# MINI_SAM_D51_017.net
KiCad netlist of a schematic drawn in EAGLE
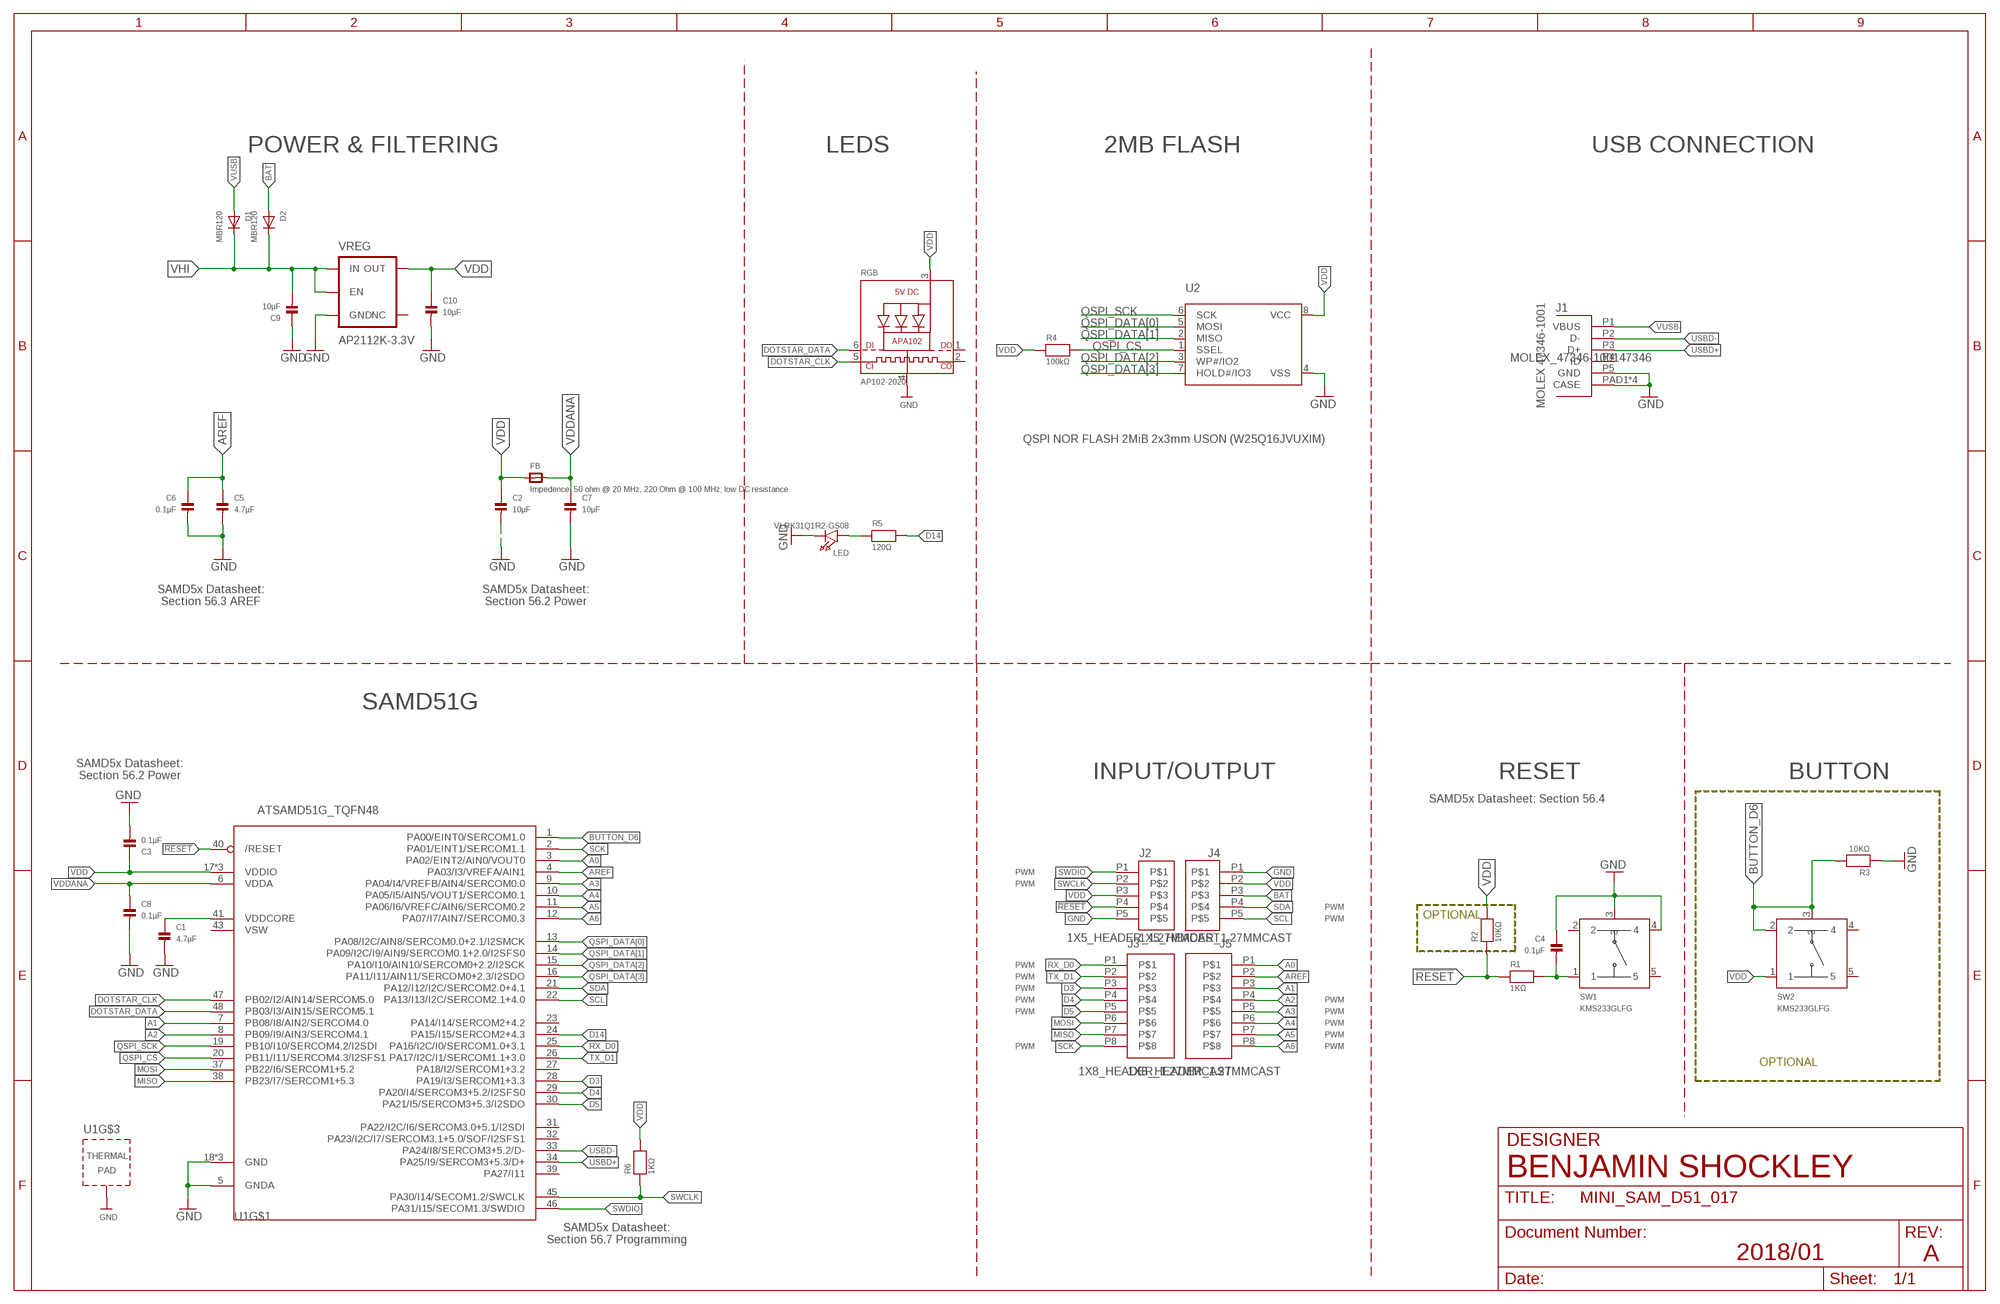
[diagram p0: schematic, sheet 1]

(export (version "E")
  (design (tool "Eeschema 10.0.6"))
  (components
    (comp (ref "C1")
      (value "4.7µF")
      (footprint "eagle-import:_0603MP")
      (libsource (lib "eagle-import") (part "CAP_CERAMIC_0603MP"))
    )
    (comp (ref "C2")
      (value "10µF")
      (footprint "eagle-import:_0603MP")
      (libsource (lib "eagle-import") (part "CAP_CERAMIC_0603MP"))
    )
    (comp (ref "C3")
      (value "0.1µF")
      (footprint "eagle-import:_0603MP")
      (libsource (lib "eagle-import") (part "CAP_CERAMIC_0603MP"))
    )
    (comp (ref "C4")
      (value "0.1µF")
      (footprint "eagle-import:_0603MP")
      (libsource (lib "eagle-import") (part "CAP_CERAMIC_0603MP"))
    )
    (comp (ref "C5")
      (value "4.7µF")
      (footprint "eagle-import:_0603MP")
      (libsource (lib "eagle-import") (part "CAP_CERAMIC_0603MP"))
    )
    (comp (ref "C6")
      (value "0.1µF")
      (footprint "eagle-import:_0603MP")
      (libsource (lib "eagle-import") (part "CAP_CERAMIC_0603MP"))
    )
    (comp (ref "C7")
      (value "10µF")
      (footprint "eagle-import:_0603MP")
      (libsource (lib "eagle-import") (part "CAP_CERAMIC_0603MP"))
    )
    (comp (ref "C8")
      (value "0.1µF")
      (footprint "eagle-import:_0603MP")
      (libsource (lib "eagle-import") (part "CAP_CERAMIC_0603MP"))
    )
    (comp (ref "C9")
      (value "10µF")
      (footprint "eagle-import:_0603MP")
      (libsource (lib "eagle-import") (part "CAP_CERAMIC_0603MP"))
    )
    (comp (ref "C10")
      (value "10µF")
      (footprint "eagle-import:_0603MP")
      (libsource (lib "eagle-import") (part "CAP_CERAMIC_0603MP"))
    )
    (comp (ref "D1")
      (value "MBR120")
      (footprint "eagle-import:SOD-123FL")
      (libsource (lib "eagle-import") (part "DIODE_SOD-123FL"))
    )
    (comp (ref "D2")
      (value "MBR120")
      (footprint "eagle-import:SOD-123FL")
      (libsource (lib "eagle-import") (part "DIODE_SOD-123FL"))
    )
    (comp (ref "FB")
      (value "Impedence: 50 ohm @ 20 MHz, 220 Ohm @ 100 MHz; low DC resistance")
      (footprint "eagle-import:_0603MP")
      (libsource (lib "eagle-import") (part "FERRITE_0603MP"))
    )
    (comp (ref "J1")
      (value "MOLEX_47346-100147346")
      (footprint "eagle-import:MOLEX_47346-1001")
      (libsource (lib "eagle-import") (part "MOLEX_47346-100147346"))
    )
    (comp (ref "J2")
      (value "1X5_HEADER_1.27MMCAST")
      (footprint "eagle-import:1X5_HEADER_1.27MM_CASTELLATED")
      (libsource (lib "eagle-import") (part "1X5_HEADER_1.27MMCAST"))
    )
    (comp (ref "J3")
      (value "1X8_HEADER_1.27MMCAST")
      (footprint "eagle-import:1X8_HEADER_1.27MM_CASTELLATED")
      (libsource (lib "eagle-import") (part "1X8_HEADER_1.27MMCAST"))
    )
    (comp (ref "J4")
      (value "1X5_HEADER_1.27MMCAST")
      (footprint "eagle-import:1X5_HEADER_1.27MM_CASTELLATED")
      (libsource (lib "eagle-import") (part "1X5_HEADER_1.27MMCAST"))
    )
    (comp (ref "J5")
      (value "1X8_HEADER_1.27MMCAST")
      (footprint "eagle-import:1X8_HEADER_1.27MM_CASTELLATED")
      (libsource (lib "eagle-import") (part "1X8_HEADER_1.27MMCAST"))
    )
    (comp (ref "LED")
      (value "VLRK31Q1R2-GS08")
      (footprint "eagle-import:REVERSE_MOUNT_LED")
      (libsource (lib "eagle-import") (part "REVERSEMOUNTLED"))
    )
    (comp (ref "R1")
      (value "1KΩ")
      (footprint "eagle-import:_0603MP")
      (libsource (lib "eagle-import") (part "RESISTOR_0603MP"))
    )
    (comp (ref "R2")
      (value "10KΩ")
      (footprint "eagle-import:_0603MP")
      (libsource (lib "eagle-import") (part "RESISTOR_0603MP"))
    )
    (comp (ref "R3")
      (value "10KΩ")
      (footprint "eagle-import:_0603MP")
      (libsource (lib "eagle-import") (part "RESISTOR_0603MP"))
    )
    (comp (ref "R4")
      (value "100kΩ")
      (footprint "eagle-import:_0603MP")
      (libsource (lib "eagle-import") (part "RESISTOR_0603MP"))
    )
    (comp (ref "R5")
      (value "120Ω")
      (footprint "eagle-import:_0603MP")
      (libsource (lib "eagle-import") (part "RESISTOR_0603MP"))
    )
    (comp (ref "R6")
      (value "1KΩ")
      (footprint "eagle-import:_0603MP")
      (libsource (lib "eagle-import") (part "RESISTOR_0603MP"))
    )
    (comp (ref "RGB")
      (value "AP102-2020")
      (footprint "eagle-import:APA102_2020")
      (libsource (lib "eagle-import") (part "APA1022020"))
    )
    (comp (ref "SW1")
      (value "KMS233GLFG")
      (footprint "eagle-import:KMS_SWITCH")
      (libsource (lib "eagle-import") (part "KMS_SWITCHKMS"))
    )
    (comp (ref "SW2")
      (value "KMS233GLFG")
      (footprint "eagle-import:KMS_SWITCH")
      (libsource (lib "eagle-import") (part "KMS_SWITCHKMS"))
    )
    (comp (ref "U1")
      (value "ATSAMD51G_TQFN48")
      (footprint "eagle-import:TQFN48_7MM")
      (libsource (lib "eagle-import") (part "ATSAMD51G_TQFN48"))
    )
    (comp (ref "U2")
      (value "QSPI NOR FLASH 2MiB 2x3mm USON (W25Q16JVUXIM)")
      (footprint "eagle-import:USON8")
      (libsource (lib "eagle-import") (part "SPIFLASH_8PINUX"))
    )
    (comp (ref "VREG")
      (value "AP2112K-3.3V")
      (footprint "eagle-import:SOT23-5")
      (libsource (lib "eagle-import") (part "V_REG_AP2112K-3.3V"))
    )
  )
  (nets
    (net (code "1") (name "/VSW") (class "Default")
      (node (ref "U1") (pin "43") (pinfunction "VSW_43") (pintype "power_in"))
    )
    (net (code "2") (name "/~{RESET}") (class "Default")
      (node (ref "J2") (pin "P4") (pinfunction "P$4_P4") (pintype "bidirectional"))
      (node (ref "R1") (pin "1") (pinfunction "1_1") (pintype "passive"))
      (node (ref "R2") (pin "1") (pinfunction "1_1") (pintype "passive"))
      (node (ref "U1") (pin "40") (pinfunction "/RESET_40") (pintype "bidirectional"))
    )
    (net (code "3") (name "A0") (class "Default")
      (node (ref "J5") (pin "P1") (pinfunction "P$1_P1") (pintype "bidirectional"))
      (node (ref "U1") (pin "3") (pinfunction "PA02/EINT2/AIN0/VOUT0_3") (pintype "bidirectional"))
    )
    (net (code "4") (name "A1") (class "Default")
      (node (ref "J5") (pin "P3") (pinfunction "P$3_P3") (pintype "bidirectional"))
      (node (ref "U1") (pin "7") (pinfunction "PB08/I8/AIN2/SERCOM4.0_7") (pintype "bidirectional"))
    )
    (net (code "5") (name "A2") (class "Default")
      (node (ref "J5") (pin "P4") (pinfunction "P$4_P4") (pintype "bidirectional"))
      (node (ref "U1") (pin "8") (pinfunction "PB09/I9/AIN3/SERCOM4.1_8") (pintype "bidirectional"))
    )
    (net (code "6") (name "A3") (class "Default")
      (node (ref "J5") (pin "P5") (pinfunction "P$5_P5") (pintype "bidirectional"))
      (node (ref "U1") (pin "9") (pinfunction "PA04/I4/VREFB/AIN4/SERCOM0.0_9") (pintype "bidirectional"))
    )
    (net (code "7") (name "A4") (class "Default")
      (node (ref "J5") (pin "P6") (pinfunction "P$6_P6") (pintype "bidirectional"))
      (node (ref "U1") (pin "10") (pinfunction "PA05/I5/AIN5/VOUT1/SERCOM0.1_10") (pintype "bidirectional"))
    )
    (net (code "8") (name "A5") (class "Default")
      (node (ref "J5") (pin "P7") (pinfunction "P$7_P7") (pintype "bidirectional"))
      (node (ref "U1") (pin "11") (pinfunction "PA06/I6/VREFC/AIN6/SERCOM0.2_11") (pintype "bidirectional"))
    )
    (net (code "9") (name "A6") (class "Default")
      (node (ref "J5") (pin "P8") (pinfunction "P$8_P8") (pintype "bidirectional"))
      (node (ref "U1") (pin "12") (pinfunction "PA07/I7/AIN7/SERCOM0.3_12") (pintype "bidirectional"))
    )
    (net (code "10") (name "AREF") (class "Default")
      (node (ref "C5") (pin "1") (pinfunction "P$1_1") (pintype "passive"))
      (node (ref "C6") (pin "1") (pinfunction "P$1_1") (pintype "passive"))
      (node (ref "J5") (pin "P2") (pinfunction "P$2_P2") (pintype "bidirectional"))
      (node (ref "U1") (pin "4") (pinfunction "PA03/I3/VREFA/AIN1_4") (pintype "bidirectional"))
    )
    (net (code "11") (name "BAT") (class "Default")
      (node (ref "D2") (pin "A") (pinfunction "A_A") (pintype "passive"))
      (node (ref "J4") (pin "P3") (pinfunction "P$3_P3") (pintype "bidirectional"))
    )
    (net (code "12") (name "BUTTON_D6") (class "Default")
      (node (ref "R3") (pin "2") (pinfunction "2_2") (pintype "passive"))
      (node (ref "SW2") (pin "2") (pinfunction "2_2") (pintype "bidirectional"))
      (node (ref "SW2") (pin "3") (pinfunction "3_3") (pintype "bidirectional"))
      (node (ref "U1") (pin "1") (pinfunction "PA00/EINT0/SERCOM1.0_1") (pintype "bidirectional"))
    )
    (net (code "13") (name "D3") (class "Default")
      (node (ref "J3") (pin "P3") (pinfunction "P$3_P3") (pintype "bidirectional"))
      (node (ref "U1") (pin "28") (pinfunction "PA19/I3/SERCOM1+3.3_28") (pintype "bidirectional"))
    )
    (net (code "14") (name "D4") (class "Default")
      (node (ref "J3") (pin "P4") (pinfunction "P$4_P4") (pintype "bidirectional"))
      (node (ref "U1") (pin "29") (pinfunction "PA20/I4/SERCOM3+5.2/I2SFS0_29") (pintype "bidirectional"))
    )
    (net (code "15") (name "D5") (class "Default")
      (node (ref "J3") (pin "P5") (pinfunction "P$5_P5") (pintype "bidirectional"))
      (node (ref "U1") (pin "30") (pinfunction "PA21/I5/SERCOM3+5.3/I2SDO_30") (pintype "bidirectional"))
    )
    (net (code "16") (name "D14") (class "Default")
      (node (ref "R5") (pin "2") (pinfunction "2_2") (pintype "passive"))
      (node (ref "U1") (pin "24") (pinfunction "PA15/I15/SERCOM2+4.3_24") (pintype "bidirectional"))
    )
    (net (code "17") (name "DOTSTAR_CLK") (class "Default")
      (node (ref "RGB") (pin "5") (pinfunction "CKI_5") (pintype "input"))
      (node (ref "U1") (pin "47") (pinfunction "PB02/I2/AIN14/SERCOM5.0_47") (pintype "bidirectional"))
    )
    (net (code "18") (name "DOTSTAR_DATA") (class "Default")
      (node (ref "RGB") (pin "6") (pinfunction "DI_6") (pintype "input"))
      (node (ref "U1") (pin "48") (pinfunction "PB03/I3/AIN15/SERCOM5.1_48") (pintype "bidirectional"))
    )
    (net (code "19") (name "GND") (class "Default")
      (node (ref "C1") (pin "2") (pinfunction "P$2_2") (pintype "passive"))
      (node (ref "C10") (pin "2") (pinfunction "P$2_2") (pintype "passive"))
      (node (ref "C2") (pin "2") (pinfunction "P$2_2") (pintype "passive"))
      (node (ref "C3") (pin "2") (pinfunction "P$2_2") (pintype "passive"))
      (node (ref "C4") (pin "1") (pinfunction "P$1_1") (pintype "passive"))
      (node (ref "C5") (pin "2") (pinfunction "P$2_2") (pintype "passive"))
      (node (ref "C6") (pin "2") (pinfunction "P$2_2") (pintype "passive"))
      (node (ref "C7") (pin "2") (pinfunction "P$2_2") (pintype "passive"))
      (node (ref "C8") (pin "2") (pinfunction "P$2_2") (pintype "passive"))
      (node (ref "C9") (pin "1") (pinfunction "P$1_1") (pintype "passive"))
      (node (ref "J1") (pin "P5") (pinfunction "GND_P5") (pintype "power_in"))
      (node (ref "J1") (pin "PAD1") (pinfunction "CASE_PAD1") (pintype "bidirectional"))
      (node (ref "J1") (pin "PAD2") (pinfunction "CASE_PAD2") (pintype "bidirectional"))
      (node (ref "J1") (pin "PAD3") (pinfunction "CASE_PAD3") (pintype "bidirectional"))
      (node (ref "J1") (pin "PAD4") (pinfunction "CASE_PAD4") (pintype "bidirectional"))
      (node (ref "J2") (pin "P5") (pinfunction "P$5_P5") (pintype "bidirectional"))
      (node (ref "J4") (pin "P1") (pinfunction "P$1_P1") (pintype "bidirectional"))
      (node (ref "LED") (pin "C") (pinfunction "C_C") (pintype "passive"))
      (node (ref "R3") (pin "1") (pinfunction "1_1") (pintype "passive"))
      (node (ref "RGB") (pin "4") (pinfunction "GND_4") (pintype "power_in"))
      (node (ref "SW1") (pin "3") (pinfunction "3_3") (pintype "bidirectional"))
      (node (ref "SW1") (pin "4") (pinfunction "4_4") (pintype "bidirectional"))
      (node (ref "U1") (pin "18") (pinfunction "GND_18") (pintype "power_in"))
      (node (ref "U1") (pin "35") (pinfunction "GND_35") (pintype "power_in"))
      (node (ref "U1") (pin "42") (pinfunction "GND_42") (pintype "power_in"))
      (node (ref "U1") (pin "5") (pinfunction "GNDA_5") (pintype "power_in"))
      (node (ref "U1") (pin "THERMAL") (pinfunction "TP_THERMAL") (pintype "power_in"))
      (node (ref "U2") (pin "4") (pinfunction "VSS_4") (pintype "bidirectional"))
      (node (ref "VREG") (pin "2") (pinfunction "GND_2") (pintype "input"))
    )
    (net (code "20") (name "MISO") (class "Default")
      (node (ref "J3") (pin "P7") (pinfunction "P$7_P7") (pintype "bidirectional"))
      (node (ref "U1") (pin "38") (pinfunction "PB23/I7/SERCOM1+5.3_38") (pintype "bidirectional"))
    )
    (net (code "21") (name "MOSI") (class "Default")
      (node (ref "J3") (pin "P6") (pinfunction "P$6_P6") (pintype "bidirectional"))
      (node (ref "U1") (pin "37") (pinfunction "PB22/I6/SERCOM1+5.2_37") (pintype "bidirectional"))
    )
    (net (code "22") (name "Net-(C1-P$1)") (class "Default")
      (node (ref "C1") (pin "1") (pinfunction "P$1_1") (pintype "passive"))
      (node (ref "U1") (pin "41") (pinfunction "VDDCORE_41") (pintype "power_in"))
    )
    (net (code "23") (name "Net-(C4-P$2)") (class "Default")
      (node (ref "C4") (pin "2") (pinfunction "P$2_2") (pintype "passive"))
      (node (ref "R1") (pin "2") (pinfunction "2_2") (pintype "passive"))
      (node (ref "SW1") (pin "1") (pinfunction "1_1") (pintype "bidirectional"))
    )
    (net (code "24") (name "Net-(LED-PadA)") (class "Default")
      (node (ref "LED") (pin "A") (pinfunction "A_A") (pintype "passive"))
      (node (ref "R5") (pin "1") (pinfunction "1_1") (pintype "passive"))
    )
    (net (code "25") (name "QSPI_CS") (class "Default")
      (node (ref "R4") (pin "2") (pinfunction "2_2") (pintype "passive"))
      (node (ref "U1") (pin "20") (pinfunction "PB11/I11/SERCOM4.3/I2SFS1_20") (pintype "bidirectional"))
      (node (ref "U2") (pin "1") (pinfunction "SSEL_1") (pintype "bidirectional"))
    )
    (net (code "26") (name "QSPI_DATA[0]") (class "Default")
      (node (ref "U1") (pin "13") (pinfunction "PA08/I2C/AIN8/SERCOM0.0+2.1/I2SMCK_13") (pintype "bidirectional"))
      (node (ref "U2") (pin "5") (pinfunction "MOSI_5") (pintype "bidirectional"))
    )
    (net (code "27") (name "QSPI_DATA[1]") (class "Default")
      (node (ref "U1") (pin "14") (pinfunction "PA09/I2C/I9/AIN9/SERCOM0.1+2.0/I2SFS0_14") (pintype "bidirectional"))
      (node (ref "U2") (pin "2") (pinfunction "MISO_2") (pintype "bidirectional"))
    )
    (net (code "28") (name "QSPI_DATA[2]") (class "Default")
      (node (ref "U1") (pin "15") (pinfunction "PA10/I10/AIN10/SERCOM0+2.2/I2SCK_15") (pintype "bidirectional"))
      (node (ref "U2") (pin "3") (pinfunction "WP#/IO2_3") (pintype "bidirectional"))
    )
    (net (code "29") (name "QSPI_DATA[3]") (class "Default")
      (node (ref "U1") (pin "16") (pinfunction "PA11/I11/AIN11/SERCOM0+2.3/I2SDO_16") (pintype "bidirectional"))
      (node (ref "U2") (pin "7") (pinfunction "HOLD#/IO3_7") (pintype "bidirectional"))
    )
    (net (code "30") (name "QSPI_SCK") (class "Default")
      (node (ref "U1") (pin "19") (pinfunction "PB10/I10/SERCOM4.2/I2SDI_19") (pintype "bidirectional"))
      (node (ref "U2") (pin "6") (pinfunction "SCK_6") (pintype "bidirectional"))
    )
    (net (code "31") (name "RX_D0") (class "Default")
      (node (ref "J3") (pin "P1") (pinfunction "P$1_P1") (pintype "bidirectional"))
      (node (ref "U1") (pin "25") (pinfunction "PA16/I2C/I0/SERCOM1.0+3.1_25") (pintype "bidirectional"))
    )
    (net (code "32") (name "SCK") (class "Default")
      (node (ref "J3") (pin "P8") (pinfunction "P$8_P8") (pintype "bidirectional"))
      (node (ref "U1") (pin "2") (pinfunction "PA01/EINT1/SERCOM1.1_2") (pintype "bidirectional"))
    )
    (net (code "33") (name "SCL") (class "Default")
      (node (ref "J4") (pin "P5") (pinfunction "P$5_P5") (pintype "bidirectional"))
      (node (ref "U1") (pin "22") (pinfunction "PA13/I13/I2C/SERCOM2.1+4.0_22") (pintype "bidirectional"))
    )
    (net (code "34") (name "SDA") (class "Default")
      (node (ref "J4") (pin "P4") (pinfunction "P$4_P4") (pintype "bidirectional"))
      (node (ref "U1") (pin "21") (pinfunction "PA12/I12/I2C/SERCOM2.0+4.1_21") (pintype "bidirectional"))
    )
    (net (code "35") (name "SWCLK") (class "Default")
      (node (ref "J2") (pin "P2") (pinfunction "P$2_P2") (pintype "bidirectional"))
      (node (ref "R6") (pin "1") (pinfunction "1_1") (pintype "passive"))
      (node (ref "U1") (pin "45") (pinfunction "PA30/I14/SECOM1.2/SWCLK_45") (pintype "bidirectional"))
    )
    (net (code "36") (name "SWDIO") (class "Default")
      (node (ref "J2") (pin "P1") (pinfunction "P$1_P1") (pintype "bidirectional"))
      (node (ref "U1") (pin "46") (pinfunction "PA31/I15/SECOM1.3/SWDIO_46") (pintype "bidirectional"))
    )
    (net (code "37") (name "TX_D1") (class "Default")
      (node (ref "J3") (pin "P2") (pinfunction "P$2_P2") (pintype "bidirectional"))
      (node (ref "U1") (pin "26") (pinfunction "PA17/I2C/I1/SERCOM1.1+3.0_26") (pintype "bidirectional"))
    )
    (net (code "38") (name "USBD+") (class "Default")
      (node (ref "J1") (pin "P3") (pinfunction "D+_P3") (pintype "bidirectional"))
      (node (ref "U1") (pin "34") (pinfunction "PA25/I9/SERCOM3+5.3/D+_34") (pintype "bidirectional"))
    )
    (net (code "39") (name "USBD-") (class "Default")
      (node (ref "J1") (pin "P2") (pinfunction "D-_P2") (pintype "bidirectional"))
      (node (ref "U1") (pin "33") (pinfunction "PA24/I8/SERCOM3+5.2/D-_33") (pintype "bidirectional"))
    )
    (net (code "40") (name "VDD") (class "Default")
      (node (ref "C10") (pin "1") (pinfunction "P$1_1") (pintype "passive"))
      (node (ref "C2") (pin "1") (pinfunction "P$1_1") (pintype "passive"))
      (node (ref "C3") (pin "1") (pinfunction "P$1_1") (pintype "passive"))
      (node (ref "FB") (pin "1") (pinfunction "P$1_1") (pintype "passive"))
      (node (ref "J2") (pin "P3") (pinfunction "P$3_P3") (pintype "bidirectional"))
      (node (ref "J4") (pin "P2") (pinfunction "P$2_P2") (pintype "bidirectional"))
      (node (ref "R2") (pin "2") (pinfunction "2_2") (pintype "passive"))
      (node (ref "R4") (pin "1") (pinfunction "1_1") (pintype "passive"))
      (node (ref "R6") (pin "2") (pinfunction "2_2") (pintype "passive"))
      (node (ref "RGB") (pin "3") (pinfunction "VDD_3") (pintype "power_in"))
      (node (ref "SW2") (pin "1") (pinfunction "1_1") (pintype "bidirectional"))
      (node (ref "U1") (pin "17") (pinfunction "VDDIO_17") (pintype "power_in"))
      (node (ref "U1") (pin "36") (pinfunction "VDDIO_36") (pintype "power_in"))
      (node (ref "U1") (pin "44") (pinfunction "VDDIO_44") (pintype "power_in"))
      (node (ref "U2") (pin "8") (pinfunction "VCC_8") (pintype "bidirectional"))
      (node (ref "VREG") (pin "5") (pinfunction "OUT_5") (pintype "passive"))
    )
    (net (code "41") (name "VDDANA") (class "Default")
      (node (ref "C7") (pin "1") (pinfunction "P$1_1") (pintype "passive"))
      (node (ref "C8") (pin "1") (pinfunction "P$1_1") (pintype "passive"))
      (node (ref "FB") (pin "2") (pinfunction "P$2_2") (pintype "passive"))
      (node (ref "U1") (pin "6") (pinfunction "VDDA_6") (pintype "power_in"))
    )
    (net (code "42") (name "VHI") (class "Default")
      (node (ref "C9") (pin "2") (pinfunction "P$2_2") (pintype "passive"))
      (node (ref "D1") (pin "C") (pinfunction "C_C") (pintype "passive"))
      (node (ref "D2") (pin "C") (pinfunction "C_C") (pintype "passive"))
      (node (ref "VREG") (pin "1") (pinfunction "IN_1") (pintype "input"))
      (node (ref "VREG") (pin "3") (pinfunction "EN_3") (pintype "input"))
    )
    (net (code "43") (name "VUSB") (class "Default")
      (node (ref "D1") (pin "A") (pinfunction "A_A") (pintype "passive"))
      (node (ref "J1") (pin "P1") (pinfunction "VBUS_P1") (pintype "power_in"))
    )
    (net (code "44") (name "unconnected-(J1-ID-PadP4)") (class "Default")
      (node (ref "J1") (pin "P4") (pinfunction "ID_P4") (pintype "bidirectional"))
    )
    (net (code "45") (name "unconnected-(RGB-CKO-Pad2)") (class "Default")
      (node (ref "RGB") (pin "2") (pinfunction "CKO_2") (pintype "output"))
    )
    (net (code "46") (name "unconnected-(RGB-DO-Pad1)") (class "Default")
      (node (ref "RGB") (pin "1") (pinfunction "DO_1") (pintype "output"))
    )
    (net (code "47") (name "unconnected-(SW1-Pad2)") (class "Default")
      (node (ref "SW1") (pin "2") (pinfunction "2_2") (pintype "bidirectional"))
    )
    (net (code "48") (name "unconnected-(SW1-Pad5)") (class "Default")
      (node (ref "SW1") (pin "5") (pinfunction "5_5") (pintype "bidirectional"))
    )
    (net (code "49") (name "unconnected-(SW2-Pad4)") (class "Default")
      (node (ref "SW2") (pin "4") (pinfunction "4_4") (pintype "bidirectional"))
    )
    (net (code "50") (name "unconnected-(SW2-Pad5)") (class "Default")
      (node (ref "SW2") (pin "5") (pinfunction "5_5") (pintype "bidirectional"))
    )
    (net (code "51") (name "unconnected-(U1A-PA14{slash}I14{slash}SERCOM2+4.2-Pad23)") (class "Default")
      (node (ref "U1") (pin "23") (pinfunction "PA14/I14/SERCOM2+4.2_23") (pintype "bidirectional"))
    )
    (net (code "52") (name "unconnected-(U1A-PA18{slash}I2{slash}SERCOM1+3.2-Pad27)") (class "Default")
      (node (ref "U1") (pin "27") (pinfunction "PA18/I2/SERCOM1+3.2_27") (pintype "bidirectional"))
    )
    (net (code "53") (name "unconnected-(U1A-PA22{slash}I2C{slash}I6{slash}SERCOM3.0+5.1{slash}I2SDI-Pad31)") (class "Default")
      (node (ref "U1") (pin "31") (pinfunction "PA22/I2C/I6/SERCOM3.0+5.1/I2SDI_31") (pintype "bidirectional"))
    )
    (net (code "54") (name "unconnected-(U1A-PA23{slash}I2C{slash}I7{slash}SERCOM3.1+5.0{slash}SOF{slash}I2SFS1-Pad32)") (class "Default")
      (node (ref "U1") (pin "32") (pinfunction "PA23/I2C/I7/SERCOM3.1+5.0/SOF/I2SFS1_32") (pintype "bidirectional"))
    )
    (net (code "55") (name "unconnected-(U1A-PA27{slash}I11-Pad39)") (class "Default")
      (node (ref "U1") (pin "39") (pinfunction "PA27/I11_39") (pintype "bidirectional"))
    )
    (net (code "56") (name "unconnected-(VREG-NC-Pad4)") (class "Default")
      (node (ref "VREG") (pin "4") (pinfunction "NC_4") (pintype "input"))
    )
  )
)
